# DoorBell.net
KiCad netlist of a schematic drawn in EAGLE
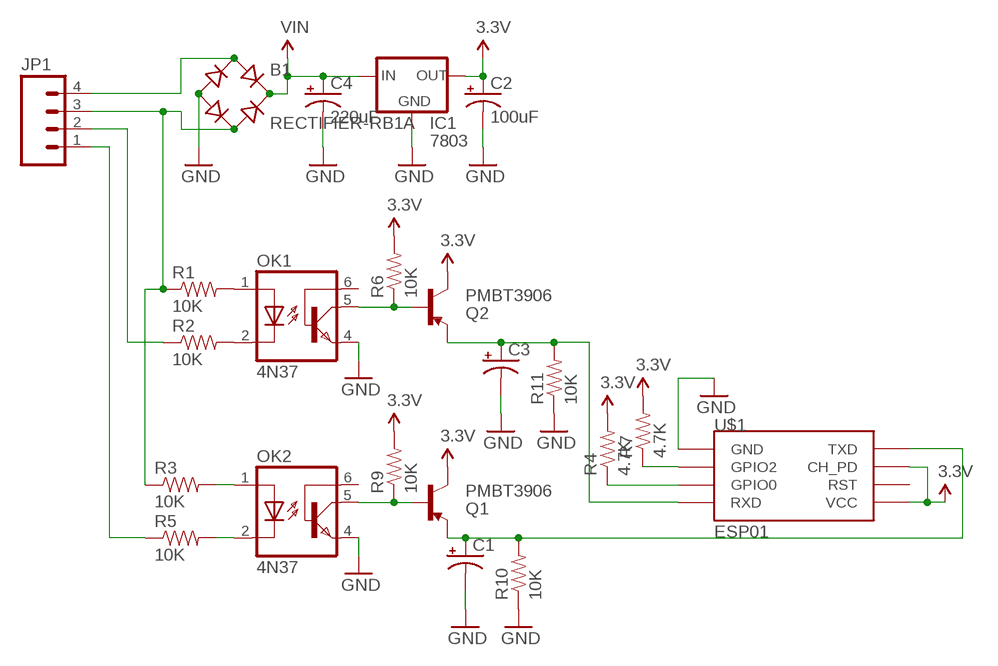
[diagram p0: schematic, sheet 1]

(export (version "E")
  (design (tool "Eeschema 10.0.6"))
  (components
    (comp (ref "B1")
      (value "RECTIFIER-RB1A")
      (footprint "eagle-import:RB1A")
      (libsource (lib "eagle-import") (part "RECTIFIER-RB1A"))
    )
    (comp (ref "C1")
      (value "CAP_POLPTH2")
      (footprint "eagle-import:CPOL-RADIAL-10UF-25V")
      (libsource (lib "eagle-import") (part "CAP_POLPTH2"))
    )
    (comp (ref "C2")
      (value "100uF")
      (footprint "eagle-import:CPOL-RADIAL-10UF-25V")
      (libsource (lib "eagle-import") (part "CAP_POLPTH2"))
    )
    (comp (ref "C3")
      (value "CAP_POLPTH2")
      (footprint "eagle-import:CPOL-RADIAL-10UF-25V")
      (libsource (lib "eagle-import") (part "CAP_POLPTH2"))
    )
    (comp (ref "C4")
      (value "220uF")
      (footprint "eagle-import:CPOL-RADIAL-1000UF-63V")
      (libsource (lib "eagle-import") (part "CAP_POLPTH3"))
    )
    (comp (ref "IC1")
      (value "7803")
      (footprint "eagle-import:TO-220-ALT")
      (libsource (lib "eagle-import") (part "V_REG_78XX-TO-220"))
    )
    (comp (ref "JP1")
      (value "M04SCREW")
      (footprint "eagle-import:SCREWTERMINAL-3.5MM-4")
      (libsource (lib "eagle-import") (part "M04SCREW"))
    )
    (comp (ref "OK1")
      (value "4N37")
      (footprint "eagle-import:DIL06")
      (fields (field (name "MF") "FAIRCHILD SEMICONDUCTOR"))
      (libsource (lib "eagle-import") (part "4N37"))
    )
    (comp (ref "OK2")
      (value "4N37")
      (footprint "eagle-import:DIL06")
      (fields (field (name "MF") "FAIRCHILD SEMICONDUCTOR"))
      (libsource (lib "eagle-import") (part "4N37"))
    )
    (comp (ref "Q1")
      (value "PMBT3906")
      (footprint "eagle-import:SOT23-3")
      (libsource (lib "eagle-import") (part "TRANSISTOR_PNPPMBT3906"))
    )
    (comp (ref "Q2")
      (value "PMBT3906")
      (footprint "eagle-import:SOT23-3")
      (libsource (lib "eagle-import") (part "TRANSISTOR_PNPPMBT3906"))
    )
    (comp (ref "R1")
      (value "10K")
      (footprint "eagle-import:AXIAL-0.1")
      (libsource (lib "eagle-import") (part "RESISTORPTH-1/4W-VERT"))
    )
    (comp (ref "R2")
      (value "10K")
      (footprint "eagle-import:AXIAL-0.1")
      (libsource (lib "eagle-import") (part "RESISTORPTH-1/4W-VERT"))
    )
    (comp (ref "R3")
      (value "10K")
      (footprint "eagle-import:AXIAL-0.1")
      (libsource (lib "eagle-import") (part "RESISTORPTH-1/4W-VERT"))
    )
    (comp (ref "R4")
      (value "4.7K")
      (footprint "eagle-import:AXIAL-0.3EZ")
      (libsource (lib "eagle-import") (part "RESISTOREZ"))
    )
    (comp (ref "R5")
      (value "10K")
      (footprint "eagle-import:AXIAL-0.1")
      (libsource (lib "eagle-import") (part "RESISTORPTH-1/4W-VERT"))
    )
    (comp (ref "R6")
      (value "10K")
      (footprint "eagle-import:AXIAL-0.1")
      (libsource (lib "eagle-import") (part "RESISTORPTH-1/4W-VERT"))
    )
    (comp (ref "R7")
      (value "4.7K")
      (footprint "eagle-import:AXIAL-0.3EZ")
      (libsource (lib "eagle-import") (part "RESISTOREZ"))
    )
    (comp (ref "R9")
      (value "10K")
      (footprint "eagle-import:AXIAL-0.1")
      (libsource (lib "eagle-import") (part "RESISTORPTH-1/4W-VERT"))
    )
    (comp (ref "R10")
      (value "10K")
      (footprint "eagle-import:AXIAL-0.1")
      (libsource (lib "eagle-import") (part "RESISTORPTH-1/4W-VERT"))
    )
    (comp (ref "R11")
      (value "10K")
      (footprint "eagle-import:AXIAL-0.1")
      (libsource (lib "eagle-import") (part "RESISTORPTH-1/4W-VERT"))
    )
    (comp (ref "U$1")
      (value "ESP01")
      (footprint "eagle-import:ESP01")
      (libsource (lib "eagle-import") (part "ESP01"))
    )
  )
  (nets
    (net (code "1") (name "3.3V") (class "Default")
      (node (ref "C2") (pin "1") (pinfunction "+_1") (pintype "passive"))
      (node (ref "IC1") (pin "OUT") (pinfunction "OUT_OUT") (pintype "output"))
      (node (ref "Q1") (pin "3") (pinfunction "C_3") (pintype "passive"))
      (node (ref "Q2") (pin "3") (pinfunction "C_3") (pintype "passive"))
      (node (ref "R4") (pin "P$2") (pinfunction "2_P$2") (pintype "passive"))
      (node (ref "R6") (pin "P$2") (pinfunction "2_P$2") (pintype "passive"))
      (node (ref "R7") (pin "P$2") (pinfunction "2_P$2") (pintype "passive"))
      (node (ref "R9") (pin "P$2") (pinfunction "2_P$2") (pintype "passive"))
      (node (ref "U$1") (pin "CH_PD") (pinfunction "CH_PD_CH_PD") (pintype "bidirectional"))
      (node (ref "U$1") (pin "VCC") (pinfunction "VCC_VCC") (pintype "bidirectional"))
    )
    (net (code "2") (name "GND") (class "Default")
      (node (ref "B1") (pin "-") (pinfunction "-_-") (pintype "passive"))
      (node (ref "C1") (pin "2") (pinfunction "-_2") (pintype "passive"))
      (node (ref "C2") (pin "2") (pinfunction "-_2") (pintype "passive"))
      (node (ref "C3") (pin "2") (pinfunction "-_2") (pintype "passive"))
      (node (ref "C4") (pin "2") (pinfunction "-_2") (pintype "passive"))
      (node (ref "IC1") (pin "GND") (pinfunction "GND_GND") (pintype "input"))
      (node (ref "OK1") (pin "4") (pinfunction "EMI_4") (pintype "passive"))
      (node (ref "OK2") (pin "4") (pinfunction "EMI_4") (pintype "passive"))
      (node (ref "R10") (pin "P$1") (pinfunction "1_P$1") (pintype "passive"))
      (node (ref "R11") (pin "P$1") (pinfunction "1_P$1") (pintype "passive"))
      (node (ref "U$1") (pin "GND") (pinfunction "GND_GND") (pintype "bidirectional"))
    )
    (net (code "3") (name "Net-(B1-PadAC1)") (class "Default")
      (node (ref "B1") (pin "AC1") (pinfunction "AC1_AC1") (pintype "passive"))
      (node (ref "JP1") (pin "4") (pinfunction "4_4") (pintype "passive"))
    )
    (net (code "4") (name "Net-(C1-+)") (class "Default")
      (node (ref "C1") (pin "1") (pinfunction "+_1") (pintype "passive"))
      (node (ref "Q1") (pin "2") (pinfunction "E_2") (pintype "passive"))
      (node (ref "R10") (pin "P$2") (pinfunction "2_P$2") (pintype "passive"))
      (node (ref "U$1") (pin "TX") (pinfunction "TXD_TX") (pintype "bidirectional"))
    )
    (net (code "5") (name "Net-(C3-+)") (class "Default")
      (node (ref "C3") (pin "1") (pinfunction "+_1") (pintype "passive"))
      (node (ref "Q2") (pin "2") (pinfunction "E_2") (pintype "passive"))
      (node (ref "R11") (pin "P$2") (pinfunction "2_P$2") (pintype "passive"))
      (node (ref "U$1") (pin "RX") (pinfunction "RXD_RX") (pintype "bidirectional"))
    )
    (net (code "6") (name "Net-(OK1-A)") (class "Default")
      (node (ref "OK1") (pin "1") (pinfunction "A_1") (pintype "passive"))
      (node (ref "R1") (pin "P$2") (pinfunction "2_P$2") (pintype "passive"))
    )
    (net (code "7") (name "Net-(OK1-C)") (class "Default")
      (node (ref "OK1") (pin "2") (pinfunction "C_2") (pintype "passive"))
      (node (ref "R2") (pin "P$2") (pinfunction "2_P$2") (pintype "passive"))
    )
    (net (code "8") (name "Net-(OK1-COL)") (class "Default")
      (node (ref "OK1") (pin "5") (pinfunction "COL_5") (pintype "passive"))
      (node (ref "Q2") (pin "1") (pinfunction "B_1") (pintype "passive"))
      (node (ref "R6") (pin "P$1") (pinfunction "1_P$1") (pintype "passive"))
    )
    (net (code "9") (name "Net-(OK2-A)") (class "Default")
      (node (ref "OK2") (pin "1") (pinfunction "A_1") (pintype "passive"))
      (node (ref "R3") (pin "P$2") (pinfunction "2_P$2") (pintype "passive"))
    )
    (net (code "10") (name "Net-(OK2-C)") (class "Default")
      (node (ref "OK2") (pin "2") (pinfunction "C_2") (pintype "passive"))
      (node (ref "R5") (pin "P$2") (pinfunction "2_P$2") (pintype "passive"))
    )
    (net (code "11") (name "Net-(OK2-COL)") (class "Default")
      (node (ref "OK2") (pin "5") (pinfunction "COL_5") (pintype "passive"))
      (node (ref "Q1") (pin "1") (pinfunction "B_1") (pintype "passive"))
      (node (ref "R9") (pin "P$1") (pinfunction "1_P$1") (pintype "passive"))
    )
    (net (code "12") (name "Net-(R1-1)") (class "Default")
      (node (ref "B1") (pin "AC2") (pinfunction "AC2_AC2") (pintype "passive"))
      (node (ref "JP1") (pin "3") (pinfunction "3_3") (pintype "passive"))
      (node (ref "R1") (pin "P$1") (pinfunction "1_P$1") (pintype "passive"))
      (node (ref "R3") (pin "P$1") (pinfunction "1_P$1") (pintype "passive"))
    )
    (net (code "13") (name "Net-(R2-1)") (class "Default")
      (node (ref "JP1") (pin "2") (pinfunction "2_2") (pintype "passive"))
      (node (ref "R2") (pin "P$1") (pinfunction "1_P$1") (pintype "passive"))
    )
    (net (code "14") (name "Net-(R4-1)") (class "Default")
      (node (ref "R4") (pin "P$1") (pinfunction "1_P$1") (pintype "passive"))
      (node (ref "U$1") (pin "GPIO0") (pinfunction "GPIO0_GPIO0") (pintype "bidirectional"))
    )
    (net (code "15") (name "Net-(R5-1)") (class "Default")
      (node (ref "JP1") (pin "1") (pinfunction "1_1") (pintype "passive"))
      (node (ref "R5") (pin "P$1") (pinfunction "1_P$1") (pintype "passive"))
    )
    (net (code "16") (name "Net-(R7-1)") (class "Default")
      (node (ref "R7") (pin "P$1") (pinfunction "1_P$1") (pintype "passive"))
      (node (ref "U$1") (pin "GPIO2") (pinfunction "GPIO2_GPIO2") (pintype "bidirectional"))
    )
    (net (code "17") (name "VIN") (class "Default")
      (node (ref "B1") (pin "+") (pinfunction "+_+") (pintype "passive"))
      (node (ref "C4") (pin "1") (pinfunction "+_1") (pintype "passive"))
      (node (ref "IC1") (pin "IN") (pinfunction "IN_IN") (pintype "input"))
    )
    (net (code "18") (name "unconnected-(OK1-BAS-Pad6)") (class "Default")
      (node (ref "OK1") (pin "6") (pinfunction "BAS_6") (pintype "passive"))
    )
    (net (code "19") (name "unconnected-(OK2-BAS-Pad6)") (class "Default")
      (node (ref "OK2") (pin "6") (pinfunction "BAS_6") (pintype "passive"))
    )
    (net (code "20") (name "unconnected-(U$1-PadRST)") (class "Default")
      (node (ref "U$1") (pin "RST") (pinfunction "RST_RST") (pintype "bidirectional"))
    )
  )
)
